# Sheet1.net
KiCad netlist of a schematic drawn in Altium Designer
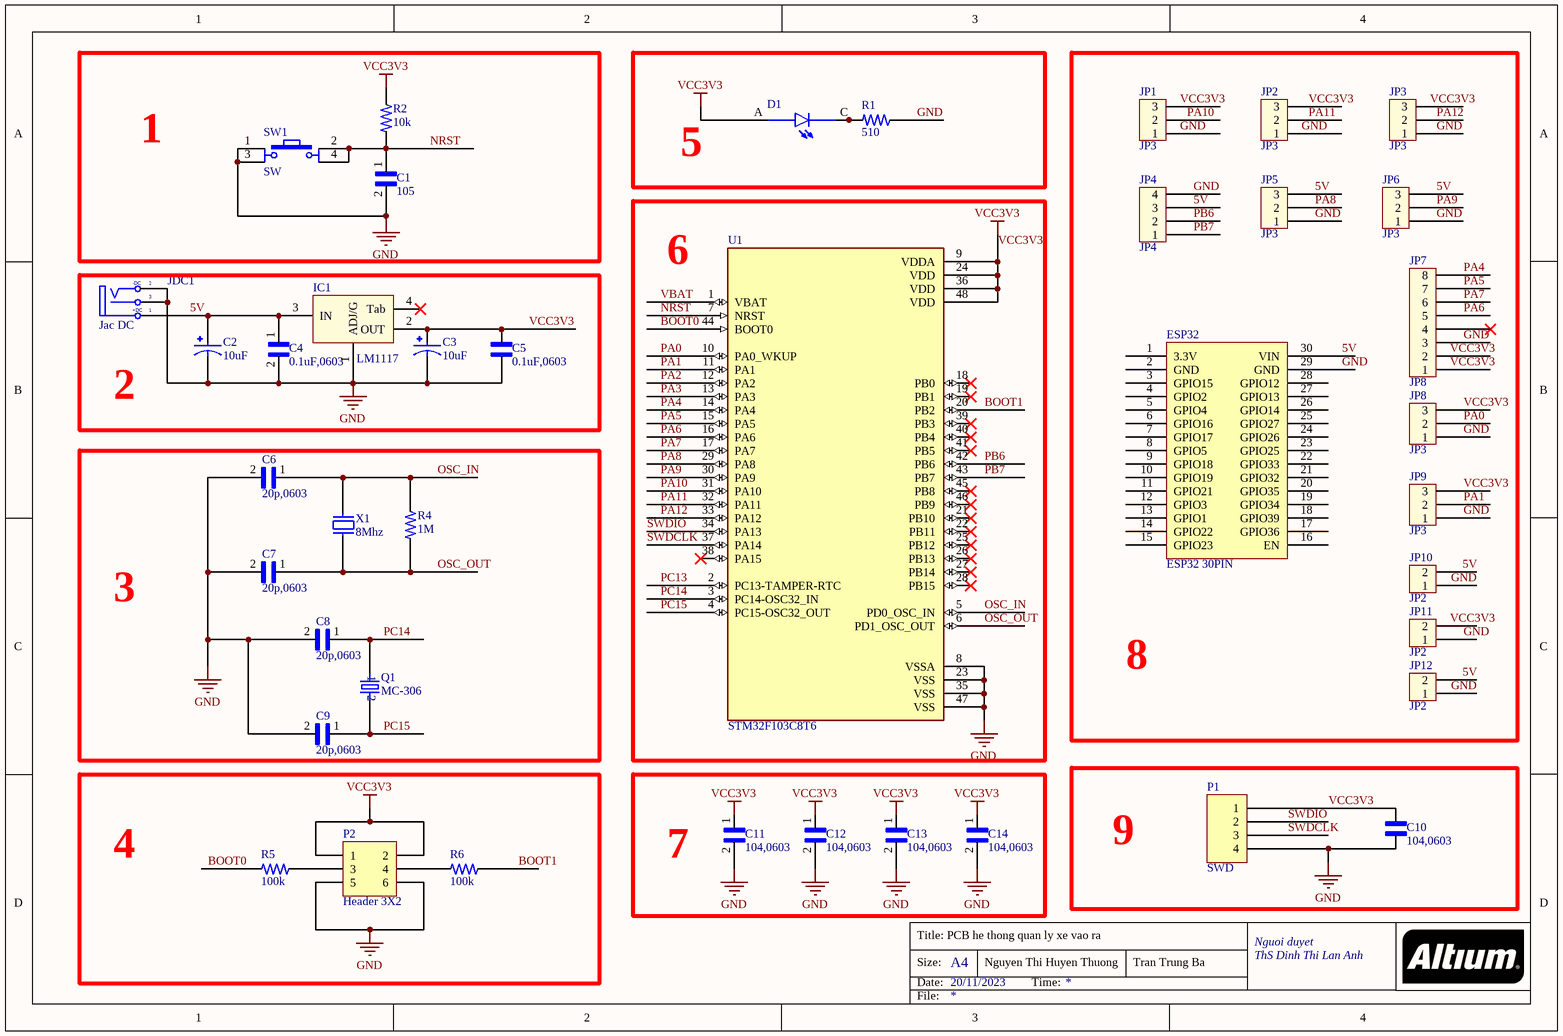
[diagram p0: Sheet1.SchDoc]

(export (version "E")
  (design (tool "Eeschema 10.0.6"))
  (components
    (comp (ref "C1")
      (value "105")
      (footprint "CAPC1608X90")
      (description "CAP CER 2700PF 50V X7R 0603")
      (fields (field (name "MP") "CC0603MRX7R9BB272"))
      (libsource (lib "") (part "CC0603MRX7R9BB272_1"))
    )
    (comp (ref "C2")
      (value "10uF")
      (footprint "CAP_EEE1EA100WAR")
      (description "10ÂµF 25V Aluminum Electrolytic Capacitors Radial, Can - SMD 1000 Hrs @ 85Â°C")
      (fields (field (name "MP") "EEE1EA100WAR") (field (name "MF") "Panasonic"))
      (libsource (lib "EEE1EA100WAR") (part "EEE1EA100WAR"))
    )
    (comp (ref "C3")
      (value "10uF")
      (footprint "CAP_EEE1EA100WAR")
      (description "10ÂµF 25V Aluminum Electrolytic Capacitors Radial, Can - SMD 1000 Hrs @ 85Â°C")
      (fields (field (name "MP") "EEE1EA100WAR") (field (name "MF") "Panasonic"))
      (libsource (lib "EEE1EA100WAR") (part "EEE1EA100WAR"))
    )
    (comp (ref "C4")
      (value "0.1uF,0603")
      (footprint "CAPC1608X90")
      (description "CAP CER 2700PF 50V X7R 0603")
      (fields (field (name "MP") "CC0603MRX7R9BB272"))
      (libsource (lib "") (part "CC0603MRX7R9BB272_1"))
    )
    (comp (ref "C5")
      (value "0.1uF,0603")
      (footprint "CAPC1608X90")
      (description "CAP CER 2700PF 50V X7R 0603")
      (fields (field (name "MP") "CC0603MRX7R9BB272"))
      (libsource (lib "") (part "CC0603MRX7R9BB272_2"))
    )
    (comp (ref "C6")
      (value "20p,0603")
      (footprint "CAPC1608X90")
      (description "CAP CER 2700PF 50V X7R 0603")
      (fields (field (name "MP") "CC0603MRX7R9BB272"))
      (libsource (lib "CC0603MRX7R9BB272") (part "CC0603MRX7R9BB272"))
    )
    (comp (ref "C7")
      (value "20p,0603")
      (footprint "CAPC1608X90")
      (description "CAP CER 2700PF 50V X7R 0603")
      (fields (field (name "MP") "CC0603MRX7R9BB272"))
      (libsource (lib "CC0603MRX7R9BB272") (part "CC0603MRX7R9BB272"))
    )
    (comp (ref "C8")
      (value "20p,0603")
      (footprint "CAPC1608X90")
      (description "CAP CER 2700PF 50V X7R 0603")
      (fields (field (name "MP") "CC0603MRX7R9BB272"))
      (libsource (lib "CC0603MRX7R9BB272") (part "CC0603MRX7R9BB272"))
    )
    (comp (ref "C9")
      (value "20p,0603")
      (footprint "CAPC1608X90")
      (description "CAP CER 2700PF 50V X7R 0603")
      (fields (field (name "MP") "CC0603MRX7R9BB272"))
      (libsource (lib "CC0603MRX7R9BB272") (part "CC0603MRX7R9BB272"))
    )
    (comp (ref "C10")
      (value "104,0603")
      (footprint "CAPC1608X90")
      (description "CAP CER 2700PF 50V X7R 0603")
      (fields (field (name "MP") "CC0603MRX7R9BB272"))
      (libsource (lib "") (part "CC0603MRX7R9BB272_2"))
    )
    (comp (ref "C11")
      (value "104,0603")
      (footprint "CAPC1608X90")
      (description "CAP CER 2700PF 50V X7R 0603")
      (fields (field (name "MP") "CC0603MRX7R9BB272"))
      (libsource (lib "") (part "CC0603MRX7R9BB272_1"))
    )
    (comp (ref "C12")
      (value "104,0603")
      (footprint "CAPC1608X90")
      (description "CAP CER 2700PF 50V X7R 0603")
      (fields (field (name "MP") "CC0603MRX7R9BB272"))
      (libsource (lib "") (part "CC0603MRX7R9BB272_1"))
    )
    (comp (ref "C13")
      (value "104,0603")
      (footprint "CAPC1608X90")
      (description "CAP CER 2700PF 50V X7R 0603")
      (fields (field (name "MP") "CC0603MRX7R9BB272"))
      (libsource (lib "") (part "CC0603MRX7R9BB272_1"))
    )
    (comp (ref "C14")
      (value "104,0603")
      (footprint "CAPC1608X90")
      (description "CAP CER 2700PF 50V X7R 0603")
      (fields (field (name "MP") "CC0603MRX7R9BB272"))
      (libsource (lib "") (part "CC0603MRX7R9BB272_1"))
    )
    (comp (ref "D1")
      (value "HSMS-C190")
      (footprint "LEDM1608X80")
      (description "Red 626nm LED Indication - Discrete 2.1V 0603 _1608 Metric_")
      (fields (field (name "MF") "Broadcom Limited"))
      (libsource (lib "ledsmd0603") (part "HSMS-C190"))
    )
    (comp (ref "ESP32")
      (value "ESP32 30PIN")
      (footprint "ESP32 DOIT 30-PIN")
      (libsource (lib "Schlib1") (part "ESP32 30PIN"))
    )
    (comp (ref "IC1")
      (value "LM1117")
      (footprint "SOT223-4N")
      (description "3v3")
      (libsource (lib "syhaunguyen") (part "LM1117"))
    )
    (comp (ref "JDC1")
      (value "Jac DC")
      (footprint "DC-IN")
      (description "Jac DC input")
      (libsource (lib "My Library") (part "DCIN"))
    )
    (comp (ref "JP1")
      (value "JP3")
      (footprint "CON3")
      (description "Connector 3")
      (libsource (lib "My Library") (part "Con3"))
    )
    (comp (ref "JP2")
      (value "JP3")
      (footprint "CON3")
      (description "Connector 3")
      (libsource (lib "My Library") (part "Con3"))
    )
    (comp (ref "JP3")
      (value "JP3")
      (footprint "CON3")
      (description "Connector 3")
      (libsource (lib "My Library") (part "Con3"))
    )
    (comp (ref "JP4")
      (value "JP4")
      (footprint "CON4")
      (description "Connector 4")
      (libsource (lib "My Library") (part "Con4"))
    )
    (comp (ref "JP5")
      (value "JP3")
      (footprint "CON3")
      (description "Connector 3")
      (libsource (lib "My Library") (part "Con3"))
    )
    (comp (ref "JP6")
      (value "JP3")
      (footprint "CON3")
      (description "Connector 3")
      (libsource (lib "My Library") (part "Con3"))
    )
    (comp (ref "JP7")
      (value "JP8")
      (footprint "CON8")
      (description "Connector 8")
      (libsource (lib "My Library") (part "Con8"))
    )
    (comp (ref "JP8")
      (value "JP3")
      (footprint "CON3")
      (description "Connector 3")
      (libsource (lib "My Library") (part "Con3"))
    )
    (comp (ref "JP9")
      (value "JP3")
      (footprint "CON3")
      (description "Connector 3")
      (libsource (lib "My Library") (part "Con3"))
    )
    (comp (ref "JP10")
      (value "JP2")
      (footprint "CON2")
      (description "Connector 2")
      (libsource (lib "My Library") (part "Con2"))
    )
    (comp (ref "JP11")
      (value "JP2")
      (footprint "CON2")
      (description "Connector 2")
      (libsource (lib "My Library") (part "Con2"))
    )
    (comp (ref "JP12")
      (value "JP2")
      (footprint "CON2")
      (description "Connector 2")
      (libsource (lib "My Library") (part "Con2"))
    )
    (comp (ref "P1")
      (value "SWD")
      (footprint "HDR1X4H")
      (description "Header, 4-Pin, Right Angle")
      (fields (field (name "PUBLISHER") "Altium Limited"))
      (libsource (lib "My Library") (part "Header 4H"))
    )
    (comp (ref "P2")
      (value "Header 3X2")
      (footprint "HDR2X3")
      (description "Header, 3-Pin, Dual row")
      (fields (field (name "PUBLISHER") "Altium Limited"))
      (libsource (lib "My Library") (part "Header 3X2"))
    )
    (comp (ref "Q1")
      (value "MC-306")
      (footprint "XT 306")
      (description "32.768kHz Â±100ppm Crystal 12.5pF 50 kOhms 4-SOJ, 5.50mm pitch")
      (fields (field (name "MF") "Aigner"))
      (libsource (lib "SnapEDAsch") (part "MC-306"))
    )
    (comp (ref "R1")
      (value "510")
      (footprint "RESC1608X50N")
      (description "RES 0.068 OHM 1% 1/8W 0603")
      (fields (field (name "TOLERANCE") "1%") (field (name "MF") "TE Connectivity"))
      (libsource (lib "res0603") (part "2176051-4"))
    )
    (comp (ref "R2")
      (value "10k")
      (footprint "RESC1608X50N")
      (description "RES 0.068 OHM 1% 1/8W 0603")
      (fields (field (name "TOLERANCE") "1%") (field (name "MF") "TE Connectivity"))
      (libsource (lib "res0603") (part "2176051-4"))
    )
    (comp (ref "R4")
      (value "1M")
      (footprint "RESC1608X50N")
      (description "RES 0.068 OHM 1% 1/8W 0603")
      (fields (field (name "TOLERANCE") "1%") (field (name "MF") "TE Connectivity"))
      (libsource (lib "res0603") (part "2176051-4"))
    )
    (comp (ref "R5")
      (value "100k")
      (footprint "RESC1608X50N")
      (description "RES 0.068 OHM 1% 1/8W 0603")
      (fields (field (name "TOLERANCE") "1%") (field (name "MF") "TE Connectivity"))
      (libsource (lib "res0603") (part "2176051-4"))
    )
    (comp (ref "R6")
      (value "100k")
      (footprint "RESC1608X50N")
      (description "RES 0.068 OHM 1% 1/8W 0603")
      (fields (field (name "TOLERANCE") "1%") (field (name "MF") "TE Connectivity"))
      (libsource (lib "res0603") (part "2176051-4"))
    )
    (comp (ref "SW1")
      (value "SW")
      (footprint "SW4")
      (description "Switch button 4 pin")
      (libsource (lib "syhaunguyen") (part "SW4"))
    )
    (comp (ref "U1")
      (value "STM32F103C8T6")
      (footprint "QFP50P900X900X160-48N")
      (description "ARMÂ® CortexÂ®-M3 STM32F1 Microcontroller IC 32-Bit 72MHz 64KB _64K x 8_ FLASH")
      (fields (field (name "MF") "STMicroelectronics"))
      (libsource (lib "SnapEDAsch") (part "STM32F103C8T6"))
    )
    (comp (ref "X1")
      (value "8Mhz")
      (footprint "XT2")
      (description "Crystal For all Crystal 2pin.")
      (libsource (lib "My Library") (part "XT2"))
    )
  )
  (nets
    (net (code "1") (name "/5V") (class "Default")
      (node (ref "C2") (pin "1") (pinfunction "1_1") (pintype "passive"))
      (node (ref "C4") (pin "1") (pinfunction "1_1") (pintype "passive"))
      (node (ref "ESP32") (pin "30") (pinfunction "VIN_30") (pintype "open_collector"))
      (node (ref "IC1") (pin "3") (pinfunction "IN_3") (pintype "passive"))
      (node (ref "JDC1") (pin "1") (pinfunction "T_1") (pintype "passive"))
      (node (ref "JP10") (pin "2") (pinfunction "2_2") (pintype "passive"))
      (node (ref "JP12") (pin "2") (pinfunction "2_2") (pintype "passive"))
      (node (ref "JP4") (pin "3") (pinfunction "3_3") (pintype "passive"))
      (node (ref "JP5") (pin "3") (pinfunction "3_3") (pintype "passive"))
      (node (ref "JP6") (pin "3") (pinfunction "3_3") (pintype "passive"))
    )
    (net (code "2") (name "/BOOT0") (class "Default")
      (node (ref "R5") (pin "2") (pinfunction "2_2") (pintype "passive"))
      (node (ref "U1") (pin "44") (pinfunction "BOOT0_44") (pintype "input"))
    )
    (net (code "3") (name "/BOOT1") (class "Default")
      (node (ref "R6") (pin "1") (pinfunction "1_1") (pintype "passive"))
      (node (ref "U1") (pin "20") (pinfunction "PB2_20") (pintype "bidirectional"))
    )
    (net (code "4") (name "/NRST") (class "Default")
      (node (ref "C1") (pin "1") (pinfunction "1_1") (pintype "passive"))
      (node (ref "R2") (pin "2") (pinfunction "2_2") (pintype "passive"))
      (node (ref "SW1") (pin "2") (pintype "passive"))
      (node (ref "SW1") (pin "4") (pintype "passive"))
      (node (ref "U1") (pin "7") (pinfunction "NRST_7") (pintype "input"))
    )
    (net (code "5") (name "/OSC_IN") (class "Default")
      (node (ref "C6") (pin "1") (pinfunction "1_1") (pintype "passive"))
      (node (ref "R4") (pin "1") (pinfunction "1_1") (pintype "passive"))
      (node (ref "U1") (pin "5") (pinfunction "PD0_OSC_IN_5") (pintype "bidirectional"))
      (node (ref "X1") (pin "2") (pinfunction "2_2") (pintype "passive"))
    )
    (net (code "6") (name "/OSC_OUT") (class "Default")
      (node (ref "C7") (pin "1") (pinfunction "1_1") (pintype "passive"))
      (node (ref "R4") (pin "2") (pinfunction "2_2") (pintype "passive"))
      (node (ref "U1") (pin "6") (pinfunction "PD1_OSC_OUT_6") (pintype "bidirectional"))
      (node (ref "X1") (pin "1") (pinfunction "1_1") (pintype "passive"))
    )
    (net (code "7") (name "/PA0") (class "Default")
      (node (ref "JP8") (pin "2") (pinfunction "2_2") (pintype "passive"))
      (node (ref "U1") (pin "10") (pinfunction "PA0_WKUP_10") (pintype "bidirectional"))
    )
    (net (code "8") (name "/PA1") (class "Default")
      (node (ref "JP9") (pin "2") (pinfunction "2_2") (pintype "passive"))
      (node (ref "U1") (pin "11") (pinfunction "PA1_11") (pintype "bidirectional"))
    )
    (net (code "9") (name "/PA2") (class "Default")
      (node (ref "U1") (pin "12") (pinfunction "PA2_12") (pintype "bidirectional"))
    )
    (net (code "10") (name "/PA3") (class "Default")
      (node (ref "U1") (pin "13") (pinfunction "PA3_13") (pintype "bidirectional"))
    )
    (net (code "11") (name "/PA4") (class "Default")
      (node (ref "JP7") (pin "8") (pinfunction "8_8") (pintype "passive"))
      (node (ref "U1") (pin "14") (pinfunction "PA4_14") (pintype "bidirectional"))
    )
    (net (code "12") (name "/PA5") (class "Default")
      (node (ref "JP7") (pin "7") (pinfunction "7_7") (pintype "passive"))
      (node (ref "U1") (pin "15") (pinfunction "PA5_15") (pintype "bidirectional"))
    )
    (net (code "13") (name "/PA6") (class "Default")
      (node (ref "JP7") (pin "5") (pinfunction "5_5") (pintype "passive"))
      (node (ref "U1") (pin "16") (pinfunction "PA6_16") (pintype "bidirectional"))
    )
    (net (code "14") (name "/PA7") (class "Default")
      (node (ref "JP7") (pin "6") (pinfunction "6_6") (pintype "passive"))
      (node (ref "U1") (pin "17") (pinfunction "PA7_17") (pintype "bidirectional"))
    )
    (net (code "15") (name "/PA8") (class "Default")
      (node (ref "JP5") (pin "2") (pinfunction "2_2") (pintype "passive"))
      (node (ref "U1") (pin "29") (pinfunction "PA8_29") (pintype "bidirectional"))
    )
    (net (code "16") (name "/PA9") (class "Default")
      (node (ref "JP6") (pin "2") (pinfunction "2_2") (pintype "passive"))
      (node (ref "U1") (pin "30") (pinfunction "PA9_30") (pintype "bidirectional"))
    )
    (net (code "17") (name "/PA10") (class "Default")
      (node (ref "JP1") (pin "2") (pinfunction "2_2") (pintype "passive"))
      (node (ref "U1") (pin "31") (pinfunction "PA10_31") (pintype "bidirectional"))
    )
    (net (code "18") (name "/PA11") (class "Default")
      (node (ref "JP2") (pin "2") (pinfunction "2_2") (pintype "passive"))
      (node (ref "U1") (pin "32") (pinfunction "PA11_32") (pintype "bidirectional"))
    )
    (net (code "19") (name "/PA12") (class "Default")
      (node (ref "JP3") (pin "2") (pinfunction "2_2") (pintype "passive"))
      (node (ref "U1") (pin "33") (pinfunction "PA12_33") (pintype "bidirectional"))
    )
    (net (code "20") (name "/PB6") (class "Default")
      (node (ref "JP4") (pin "2") (pinfunction "2_2") (pintype "passive"))
      (node (ref "U1") (pin "42") (pinfunction "PB6_42") (pintype "bidirectional"))
    )
    (net (code "21") (name "/PB7") (class "Default")
      (node (ref "JP4") (pin "1") (pinfunction "1_1") (pintype "passive"))
      (node (ref "U1") (pin "43") (pinfunction "PB7_43") (pintype "bidirectional"))
    )
    (net (code "22") (name "/PC13") (class "Default")
      (node (ref "U1") (pin "2") (pinfunction "PC13-TAMPER-RTC_2") (pintype "bidirectional"))
    )
    (net (code "23") (name "/PC14") (class "Default")
      (node (ref "C8") (pin "1") (pinfunction "1_1") (pintype "passive"))
      (node (ref "Q1") (pin "1") (pinfunction "1_1") (pintype "passive"))
      (node (ref "U1") (pin "3") (pinfunction "PC14-OSC32_IN_3") (pintype "bidirectional"))
    )
    (net (code "24") (name "/PC15") (class "Default")
      (node (ref "C9") (pin "1") (pinfunction "1_1") (pintype "passive"))
      (node (ref "Q1") (pin "4") (pinfunction "2_4") (pintype "passive"))
      (node (ref "U1") (pin "4") (pinfunction "PC15-OSC32_OUT_4") (pintype "bidirectional"))
    )
    (net (code "25") (name "/SWDCLK") (class "Default")
      (node (ref "P1") (pin "3") (pinfunction "3_3") (pintype "passive"))
      (node (ref "U1") (pin "37") (pinfunction "PA14_37") (pintype "bidirectional"))
    )
    (net (code "26") (name "/SWDIO") (class "Default")
      (node (ref "P1") (pin "2") (pinfunction "2_2") (pintype "passive"))
      (node (ref "U1") (pin "34") (pinfunction "PA13_34") (pintype "bidirectional"))
    )
    (net (code "27") (name "/VBAT") (class "Default")
      (node (ref "U1") (pin "1") (pinfunction "VBAT_1") (pintype "bidirectional"))
    )
    (net (code "28") (name "GND") (class "Default")
      (node (ref "C1") (pin "2") (pinfunction "2_2") (pintype "passive"))
      (node (ref "C10") (pin "2") (pinfunction "2_2") (pintype "passive"))
      (node (ref "C11") (pin "2") (pinfunction "2_2") (pintype "passive"))
      (node (ref "C12") (pin "2") (pinfunction "2_2") (pintype "passive"))
      (node (ref "C13") (pin "2") (pinfunction "2_2") (pintype "passive"))
      (node (ref "C14") (pin "2") (pinfunction "2_2") (pintype "passive"))
      (node (ref "C2") (pin "2") (pinfunction "2_2") (pintype "passive"))
      (node (ref "C3") (pin "2") (pinfunction "2_2") (pintype "passive"))
      (node (ref "C4") (pin "2") (pinfunction "2_2") (pintype "passive"))
      (node (ref "C5") (pin "2") (pinfunction "2_2") (pintype "passive"))
      (node (ref "C6") (pin "2") (pinfunction "2_2") (pintype "passive"))
      (node (ref "C7") (pin "2") (pinfunction "2_2") (pintype "passive"))
      (node (ref "C8") (pin "2") (pinfunction "2_2") (pintype "passive"))
      (node (ref "C9") (pin "2") (pinfunction "2_2") (pintype "passive"))
      (node (ref "ESP32") (pin "29") (pinfunction "GND_29") (pintype "power_in"))
      (node (ref "IC1") (pin "1") (pinfunction "ADJ/G_1") (pintype "passive"))
      (node (ref "JDC1") (pin "2") (pinfunction "TN_2") (pintype "passive"))
      (node (ref "JDC1") (pin "3") (pinfunction "S_3") (pintype "power_in"))
      (node (ref "JP1") (pin "1") (pinfunction "1_1") (pintype "passive"))
      (node (ref "JP10") (pin "1") (pinfunction "1_1") (pintype "passive"))
      (node (ref "JP11") (pin "1") (pinfunction "1_1") (pintype "passive"))
      (node (ref "JP12") (pin "1") (pinfunction "1_1") (pintype "passive"))
      (node (ref "JP2") (pin "1") (pinfunction "1_1") (pintype "passive"))
      (node (ref "JP3") (pin "1") (pinfunction "1_1") (pintype "passive"))
      (node (ref "JP4") (pin "4") (pinfunction "4_4") (pintype "passive"))
      (node (ref "JP5") (pin "1") (pinfunction "1_1") (pintype "passive"))
      (node (ref "JP6") (pin "1") (pinfunction "1_1") (pintype "passive"))
      (node (ref "JP7") (pin "3") (pinfunction "3_3") (pintype "passive"))
      (node (ref "JP8") (pin "1") (pinfunction "1_1") (pintype "passive"))
      (node (ref "JP9") (pin "1") (pinfunction "1_1") (pintype "passive"))
      (node (ref "P1") (pin "4") (pinfunction "4_4") (pintype "passive"))
      (node (ref "P2") (pin "5") (pinfunction "5_5") (pintype "passive"))
      (node (ref "P2") (pin "6") (pinfunction "6_6") (pintype "passive"))
      (node (ref "R1") (pin "1") (pinfunction "1_1") (pintype "passive"))
      (node (ref "SW1") (pin "1") (pintype "passive"))
      (node (ref "SW1") (pin "3") (pintype "passive"))
      (node (ref "U1") (pin "23") (pinfunction "VSS_23") (pintype "power_in"))
      (node (ref "U1") (pin "35") (pinfunction "VSS_35") (pintype "power_in"))
      (node (ref "U1") (pin "47") (pinfunction "VSS_47") (pintype "power_in"))
      (node (ref "U1") (pin "8") (pinfunction "VSSA_8") (pintype "power_in"))
    )
    (net (code "29") (name "Net-(D1-PadC)") (class "Default")
      (node (ref "D1") (pin "C") (pinfunction "C_C") (pintype "passive"))
      (node (ref "R1") (pin "2") (pinfunction "2_2") (pintype "passive"))
    )
    (net (code "30") (name "Net-(P2-Pad3)") (class "Default")
      (node (ref "P2") (pin "3") (pinfunction "3_3") (pintype "passive"))
      (node (ref "R5") (pin "1") (pinfunction "1_1") (pintype "passive"))
    )
    (net (code "31") (name "Net-(P2-Pad4)") (class "Default")
      (node (ref "P2") (pin "4") (pinfunction "4_4") (pintype "passive"))
      (node (ref "R6") (pin "2") (pinfunction "2_2") (pintype "passive"))
    )
    (net (code "32") (name "VCC3V3") (class "Default")
      (node (ref "C10") (pin "1") (pinfunction "1_1") (pintype "passive"))
      (node (ref "C11") (pin "1") (pinfunction "1_1") (pintype "passive"))
      (node (ref "C12") (pin "1") (pinfunction "1_1") (pintype "passive"))
      (node (ref "C13") (pin "1") (pinfunction "1_1") (pintype "passive"))
      (node (ref "C14") (pin "1") (pinfunction "1_1") (pintype "passive"))
      (node (ref "C3") (pin "1") (pinfunction "1_1") (pintype "passive"))
      (node (ref "C5") (pin "1") (pinfunction "1_1") (pintype "passive"))
      (node (ref "D1") (pin "A") (pinfunction "A_A") (pintype "passive"))
      (node (ref "IC1") (pin "2") (pinfunction "OUT_2") (pintype "passive"))
      (node (ref "JP1") (pin "3") (pinfunction "3_3") (pintype "passive"))
      (node (ref "JP11") (pin "2") (pinfunction "2_2") (pintype "passive"))
      (node (ref "JP2") (pin "3") (pinfunction "3_3") (pintype "passive"))
      (node (ref "JP3") (pin "3") (pinfunction "3_3") (pintype "passive"))
      (node (ref "JP7") (pin "1") (pinfunction "1_1") (pintype "passive"))
      (node (ref "JP7") (pin "2") (pinfunction "2_2") (pintype "passive"))
      (node (ref "JP8") (pin "3") (pinfunction "3_3") (pintype "passive"))
      (node (ref "JP9") (pin "3") (pinfunction "3_3") (pintype "passive"))
      (node (ref "P1") (pin "1") (pinfunction "1_1") (pintype "passive"))
      (node (ref "P2") (pin "1") (pinfunction "1_1") (pintype "passive"))
      (node (ref "P2") (pin "2") (pinfunction "2_2") (pintype "passive"))
      (node (ref "R2") (pin "1") (pinfunction "1_1") (pintype "passive"))
      (node (ref "U1") (pin "24") (pinfunction "VDD_24") (pintype "power_in"))
      (node (ref "U1") (pin "36") (pinfunction "VDD_36") (pintype "power_in"))
      (node (ref "U1") (pin "48") (pinfunction "VDD_48") (pintype "power_in"))
      (node (ref "U1") (pin "9") (pinfunction "VDDA_9") (pintype "power_in"))
    )
    (net (code "33") (name "unconnected-(ESP32-3.3V-Pad1)") (class "Default")
      (node (ref "ESP32") (pin "1") (pinfunction "3.3V_1") (pintype "open_collector"))
    )
    (net (code "34") (name "unconnected-(ESP32-EN-Pad16)") (class "Default")
      (node (ref "ESP32") (pin "16") (pinfunction "EN_16") (pintype "open_collector"))
    )
    (net (code "35") (name "unconnected-(ESP32-GND-Pad2)") (class "Default")
      (node (ref "ESP32") (pin "2") (pinfunction "GND_2") (pintype "power_in"))
    )
    (net (code "36") (name "unconnected-(ESP32-GPIO1-Pad13)") (class "Default")
      (node (ref "ESP32") (pin "13") (pinfunction "GPIO1_13") (pintype "open_collector"))
    )
    (net (code "37") (name "unconnected-(ESP32-GPIO2-Pad4)") (class "Default")
      (node (ref "ESP32") (pin "4") (pinfunction "GPIO2_4") (pintype "open_collector"))
    )
    (net (code "38") (name "unconnected-(ESP32-GPIO3-Pad12)") (class "Default")
      (node (ref "ESP32") (pin "12") (pinfunction "GPIO3_12") (pintype "open_collector"))
    )
    (net (code "39") (name "unconnected-(ESP32-GPIO4-Pad5)") (class "Default")
      (node (ref "ESP32") (pin "5") (pinfunction "GPIO4_5") (pintype "open_collector"))
    )
    (net (code "40") (name "unconnected-(ESP32-GPIO5-Pad8)") (class "Default")
      (node (ref "ESP32") (pin "8") (pinfunction "GPIO5_8") (pintype "open_collector"))
    )
    (net (code "41") (name "unconnected-(ESP32-GPIO12-Pad28)") (class "Default")
      (node (ref "ESP32") (pin "28") (pinfunction "GPIO12_28") (pintype "open_collector"))
    )
    (net (code "42") (name "unconnected-(ESP32-GPIO13-Pad27)") (class "Default")
      (node (ref "ESP32") (pin "27") (pinfunction "GPIO13_27") (pintype "open_collector"))
    )
    (net (code "43") (name "unconnected-(ESP32-GPIO14-Pad26)") (class "Default")
      (node (ref "ESP32") (pin "26") (pinfunction "GPIO14_26") (pintype "open_collector"))
    )
    (net (code "44") (name "unconnected-(ESP32-GPIO15-Pad3)") (class "Default")
      (node (ref "ESP32") (pin "3") (pinfunction "GPIO15_3") (pintype "open_collector"))
    )
    (net (code "45") (name "unconnected-(ESP32-GPIO16-Pad6)") (class "Default")
      (node (ref "ESP32") (pin "6") (pinfunction "GPIO16_6") (pintype "open_collector"))
    )
    (net (code "46") (name "unconnected-(ESP32-GPIO17-Pad7)") (class "Default")
      (node (ref "ESP32") (pin "7") (pinfunction "GPIO17_7") (pintype "open_collector"))
    )
    (net (code "47") (name "unconnected-(ESP32-GPIO18-Pad9)") (class "Default")
      (node (ref "ESP32") (pin "9") (pinfunction "GPIO18_9") (pintype "open_collector"))
    )
    (net (code "48") (name "unconnected-(ESP32-GPIO19-Pad10)") (class "Default")
      (node (ref "ESP32") (pin "10") (pinfunction "GPIO19_10") (pintype "open_collector"))
    )
    (net (code "49") (name "unconnected-(ESP32-GPIO21-Pad11)") (class "Default")
      (node (ref "ESP32") (pin "11") (pinfunction "GPIO21_11") (pintype "open_collector"))
    )
    (net (code "50") (name "unconnected-(ESP32-GPIO22-Pad14)") (class "Default")
      (node (ref "ESP32") (pin "14") (pinfunction "GPIO22_14") (pintype "open_collector"))
    )
    (net (code "51") (name "unconnected-(ESP32-GPIO23-Pad15)") (class "Default")
      (node (ref "ESP32") (pin "15") (pinfunction "GPIO23_15") (pintype "open_collector"))
    )
    (net (code "52") (name "unconnected-(ESP32-GPIO25-Pad23)") (class "Default")
      (node (ref "ESP32") (pin "23") (pinfunction "GPIO25_23") (pintype "open_collector"))
    )
    (net (code "53") (name "unconnected-(ESP32-GPIO26-Pad24)") (class "Default")
      (node (ref "ESP32") (pin "24") (pinfunction "GPIO26_24") (pintype "open_collector"))
    )
    (net (code "54") (name "unconnected-(ESP32-GPIO27-Pad25)") (class "Default")
      (node (ref "ESP32") (pin "25") (pinfunction "GPIO27_25") (pintype "open_collector"))
    )
    (net (code "55") (name "unconnected-(ESP32-GPIO32-Pad21)") (class "Default")
      (node (ref "ESP32") (pin "21") (pinfunction "GPIO32_21") (pintype "open_collector"))
    )
    (net (code "56") (name "unconnected-(ESP32-GPIO33-Pad22)") (class "Default")
      (node (ref "ESP32") (pin "22") (pinfunction "GPIO33_22") (pintype "open_collector"))
    )
    (net (code "57") (name "unconnected-(ESP32-GPIO34-Pad19)") (class "Default")
      (node (ref "ESP32") (pin "19") (pinfunction "GPIO34_19") (pintype "open_collector"))
    )
    (net (code "58") (name "unconnected-(ESP32-GPIO35-Pad20)") (class "Default")
      (node (ref "ESP32") (pin "20") (pinfunction "GPIO35_20") (pintype "open_collector"))
    )
    (net (code "59") (name "unconnected-(ESP32-GPIO36-Pad17)") (class "Default")
      (node (ref "ESP32") (pin "17") (pinfunction "GPIO36_17") (pintype "open_collector"))
    )
    (net (code "60") (name "unconnected-(ESP32-GPIO39-Pad18)") (class "Default")
      (node (ref "ESP32") (pin "18") (pinfunction "GPIO39_18") (pintype "open_collector"))
    )
    (net (code "61") (name "unconnected-(IC1-Tab-Pad4)") (class "Default")
      (node (ref "IC1") (pin "4") (pinfunction "Tab_4") (pintype "passive+no_connect"))
    )
    (net (code "62") (name "unconnected-(JP7-Pad4)") (class "Default")
      (node (ref "JP7") (pin "4") (pinfunction "4_4") (pintype "passive+no_connect"))
    )
    (net (code "63") (name "unconnected-(U1-PA15-Pad38)") (class "Default")
      (node (ref "U1") (pin "38") (pinfunction "PA15_38") (pintype "bidirectional+no_connect"))
    )
    (net (code "64") (name "unconnected-(U1-PB0-Pad18)") (class "Default")
      (node (ref "U1") (pin "18") (pinfunction "PB0_18") (pintype "bidirectional+no_connect"))
    )
    (net (code "65") (name "unconnected-(U1-PB1-Pad19)") (class "Default")
      (node (ref "U1") (pin "19") (pinfunction "PB1_19") (pintype "bidirectional+no_connect"))
    )
    (net (code "66") (name "unconnected-(U1-PB3-Pad39)") (class "Default")
      (node (ref "U1") (pin "39") (pinfunction "PB3_39") (pintype "bidirectional+no_connect"))
    )
    (net (code "67") (name "unconnected-(U1-PB4-Pad40)") (class "Default")
      (node (ref "U1") (pin "40") (pinfunction "PB4_40") (pintype "bidirectional+no_connect"))
    )
    (net (code "68") (name "unconnected-(U1-PB5-Pad41)") (class "Default")
      (node (ref "U1") (pin "41") (pinfunction "PB5_41") (pintype "bidirectional+no_connect"))
    )
    (net (code "69") (name "unconnected-(U1-PB8-Pad45)") (class "Default")
      (node (ref "U1") (pin "45") (pinfunction "PB8_45") (pintype "bidirectional+no_connect"))
    )
    (net (code "70") (name "unconnected-(U1-PB9-Pad46)") (class "Default")
      (node (ref "U1") (pin "46") (pinfunction "PB9_46") (pintype "bidirectional+no_connect"))
    )
    (net (code "71") (name "unconnected-(U1-PB10-Pad21)") (class "Default")
      (node (ref "U1") (pin "21") (pinfunction "PB10_21") (pintype "bidirectional+no_connect"))
    )
    (net (code "72") (name "unconnected-(U1-PB11-Pad22)") (class "Default")
      (node (ref "U1") (pin "22") (pinfunction "PB11_22") (pintype "bidirectional+no_connect"))
    )
    (net (code "73") (name "unconnected-(U1-PB12-Pad25)") (class "Default")
      (node (ref "U1") (pin "25") (pinfunction "PB12_25") (pintype "bidirectional+no_connect"))
    )
    (net (code "74") (name "unconnected-(U1-PB13-Pad26)") (class "Default")
      (node (ref "U1") (pin "26") (pinfunction "PB13_26") (pintype "bidirectional+no_connect"))
    )
    (net (code "75") (name "unconnected-(U1-PB14-Pad27)") (class "Default")
      (node (ref "U1") (pin "27") (pinfunction "PB14_27") (pintype "bidirectional+no_connect"))
    )
    (net (code "76") (name "unconnected-(U1-PB15-Pad28)") (class "Default")
      (node (ref "U1") (pin "28") (pinfunction "PB15_28") (pintype "bidirectional+no_connect"))
    )
  )
)
